# PCB-Converter-RFM95W.net
KiCad netlist of a schematic drawn in Altium Designer
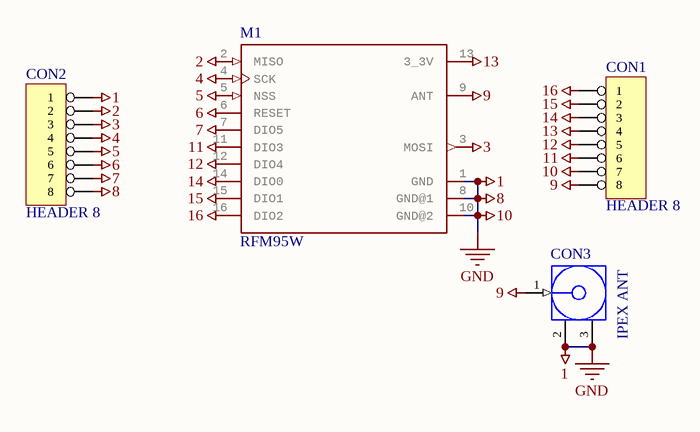
[diagram p0: PCB-Converter-RFM95W.SchDoc]

(export (version "E")
  (design (tool "Eeschema 10.0.6"))
  (components
    (comp (ref "CON1")
      (value "HEADER 8")
      (footprint "SIP 3D 8")
      (libsource (lib "CONNECTOR") (part "HEADER 8"))
    )
    (comp (ref "CON2") (value "HEADER 8") (footprint "SIP 3D 8") (libsource (lib "") (part "HEADER 8_1")))
    (comp (ref "CON3")
      (value "IPEX ANT")
      (footprint "IPEX ANT")
      (description "SMD Male Connector IPEX Antenna IPX 20279-001E")
      (libsource (lib "CONNECTOR") (part "IPEX ANT"))
    )
    (comp (ref "M1")
      (value "RFM95W")
      (footprint "LoRa RFM95W")
      (description "HOPERF LoRa RFM95W")
      (libsource (lib "MODUL") (part "LoRa RFM95W"))
    )
  )
  (nets
    (net (code "1") (name "1") (class "Default")
      (node (ref "CON1") (pin "7") (pinfunction "7_7") (pintype "passive"))
      (node (ref "CON2") (pin "1") (pinfunction "1_1") (pintype "passive"))
      (node (ref "CON2") (pin "8") (pinfunction "8_8") (pintype "passive"))
      (node (ref "CON3") (pin "2") (pinfunction "GND_2") (pintype "power_in"))
      (node (ref "CON3") (pin "3") (pinfunction "GND_3") (pintype "power_in"))
      (node (ref "M1") (pin "1") (pinfunction "GND_1") (pintype "power_in"))
      (node (ref "M1") (pin "10") (pinfunction "GND@2_10") (pintype "power_in"))
      (node (ref "M1") (pin "8") (pinfunction "GND@1_8") (pintype "power_in"))
    )
    (net (code "2") (name "2") (class "Default")
      (node (ref "CON2") (pin "2") (pinfunction "2_2") (pintype "passive"))
      (node (ref "M1") (pin "2") (pinfunction "MISO_2") (pintype "input"))
    )
    (net (code "3") (name "3") (class "Default")
      (node (ref "CON2") (pin "3") (pinfunction "3_3") (pintype "passive"))
      (node (ref "M1") (pin "3") (pinfunction "MOSI_3") (pintype "output"))
    )
    (net (code "4") (name "4") (class "Default")
      (node (ref "CON2") (pin "4") (pinfunction "4_4") (pintype "passive"))
      (node (ref "M1") (pin "4") (pinfunction "SCK_4") (pintype "input"))
    )
    (net (code "5") (name "5") (class "Default")
      (node (ref "CON2") (pin "5") (pinfunction "5_5") (pintype "passive"))
      (node (ref "M1") (pin "5") (pinfunction "NSS_5") (pintype "input"))
    )
    (net (code "6") (name "6") (class "Default")
      (node (ref "CON2") (pin "6") (pinfunction "6_6") (pintype "passive"))
      (node (ref "M1") (pin "6") (pinfunction "RESET_6") (pintype "bidirectional"))
    )
    (net (code "7") (name "7") (class "Default")
      (node (ref "CON2") (pin "7") (pinfunction "7_7") (pintype "passive"))
      (node (ref "M1") (pin "7") (pinfunction "DIO5_7") (pintype "bidirectional"))
    )
    (net (code "8") (name "9") (class "Default")
      (node (ref "CON1") (pin "8") (pinfunction "8_8") (pintype "passive"))
      (node (ref "CON3") (pin "1") (pinfunction "Signal_1") (pintype "input"))
      (node (ref "M1") (pin "9") (pinfunction "ANT_9") (pintype "passive"))
    )
    (net (code "9") (name "11") (class "Default")
      (node (ref "CON1") (pin "6") (pinfunction "6_6") (pintype "passive"))
      (node (ref "M1") (pin "11") (pinfunction "DIO3_11") (pintype "bidirectional"))
    )
    (net (code "10") (name "12") (class "Default")
      (node (ref "CON1") (pin "5") (pinfunction "5_5") (pintype "passive"))
      (node (ref "M1") (pin "12") (pinfunction "DIO4_12") (pintype "bidirectional"))
    )
    (net (code "11") (name "13") (class "Default")
      (node (ref "CON1") (pin "4") (pinfunction "4_4") (pintype "passive"))
      (node (ref "M1") (pin "13") (pinfunction "3_3V_13") (pintype "power_in"))
    )
    (net (code "12") (name "14") (class "Default")
      (node (ref "CON1") (pin "3") (pinfunction "3_3") (pintype "passive"))
      (node (ref "M1") (pin "14") (pinfunction "DIO0_14") (pintype "bidirectional"))
    )
    (net (code "13") (name "15") (class "Default")
      (node (ref "CON1") (pin "2") (pinfunction "2_2") (pintype "passive"))
      (node (ref "M1") (pin "15") (pinfunction "DIO1_15") (pintype "bidirectional"))
    )
    (net (code "14") (name "16") (class "Default")
      (node (ref "CON1") (pin "1") (pinfunction "1_1") (pintype "passive"))
      (node (ref "M1") (pin "16") (pinfunction "DIO2_16") (pintype "bidirectional"))
    )
  )
)
